# 9_3_2_detector_booster.net
KiCad netlist of a schematic drawn in EAGLE
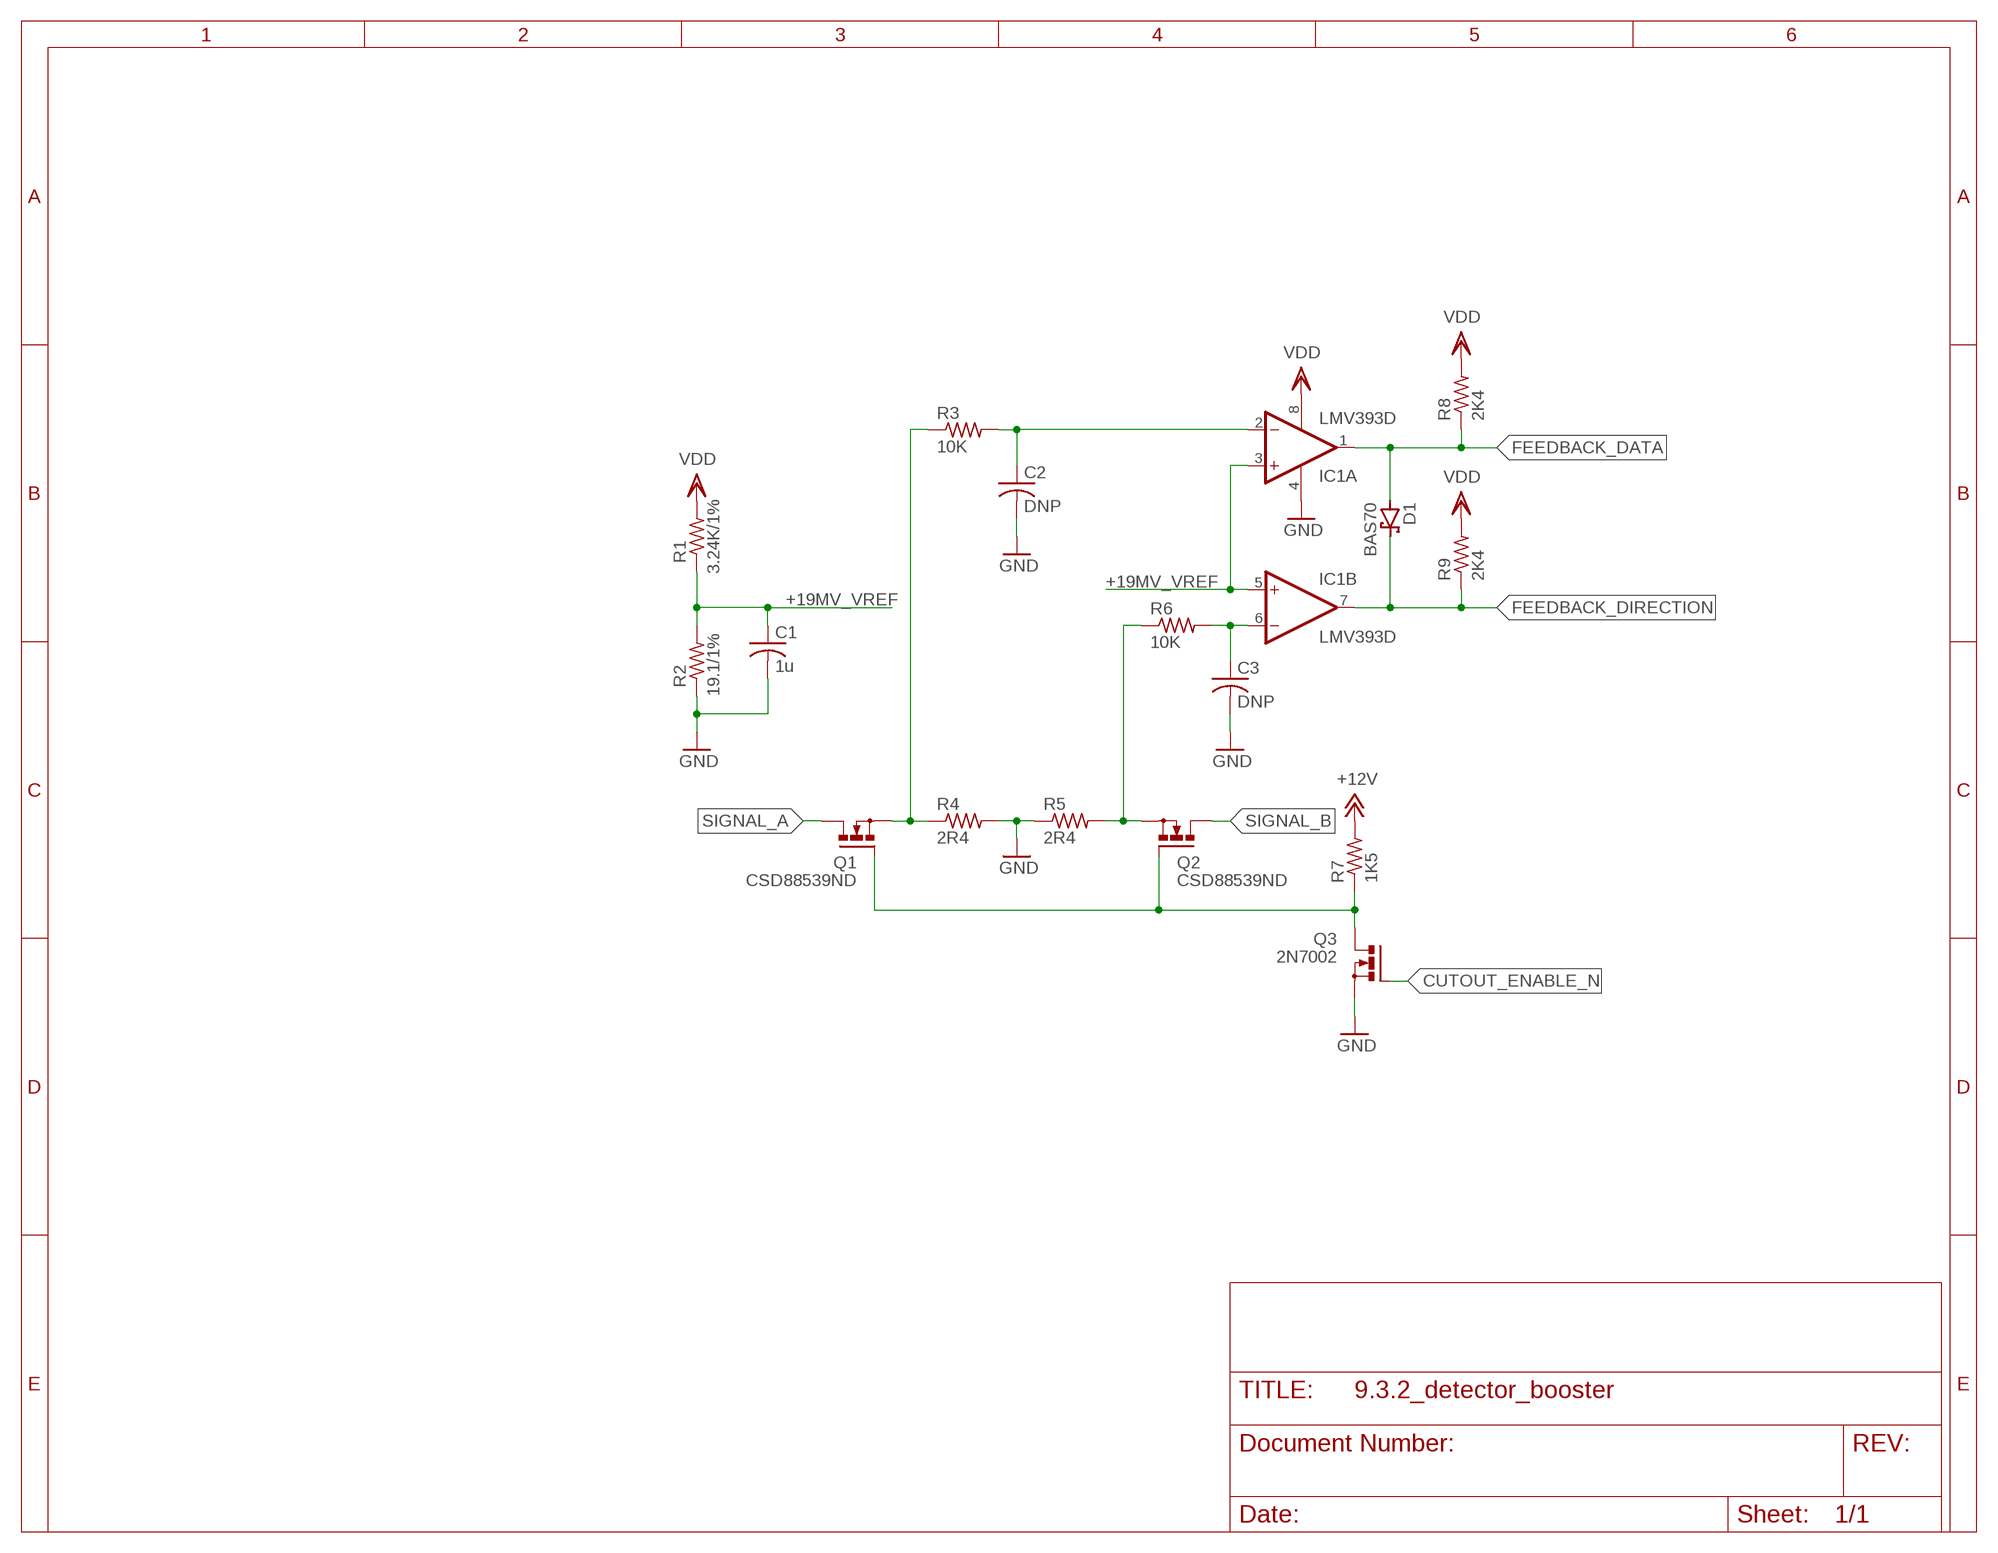
[diagram p0: schematic, sheet 1]

(export (version "E")
  (design (tool "Eeschema 10.0.6"))
  (components
    (comp (ref "C1")
      (value "1u")
      (footprint "eagle-import:C0402")
      (libsource (lib "eagle-import") (part "C-USC0402"))
    )
    (comp (ref "C2")
      (value "DNP")
      (footprint "eagle-import:C0402")
      (libsource (lib "eagle-import") (part "C-USC0402"))
    )
    (comp (ref "C3")
      (value "DNP")
      (footprint "eagle-import:C0402")
      (libsource (lib "eagle-import") (part "C-USC0402"))
    )
    (comp (ref "D1")
      (value "BAS70")
      (footprint "eagle-import:SOT23")
      (libsource (lib "eagle-import") (part "BAS70"))
    )
    (comp (ref "IC1")
      (value "LMV393D")
      (footprint "eagle-import:SO08")
      (libsource (lib "eagle-import") (part "LM393D"))
    )
    (comp (ref "Q1")
      (value "CSD88539ND")
      (footprint "eagle-import:TO220BV")
      (libsource (lib "eagle-import") (part "IRF512"))
    )
    (comp (ref "Q2")
      (value "CSD88539ND")
      (footprint "eagle-import:TO220BV")
      (libsource (lib "eagle-import") (part "IRF512"))
    )
    (comp (ref "Q3")
      (value "2N7002")
      (footprint "eagle-import:TO220BV")
      (libsource (lib "eagle-import") (part "IRF512"))
    )
    (comp (ref "R1")
      (value "3.24K/1%")
      (footprint "eagle-import:R0402")
      (libsource (lib "eagle-import") (part "R-US_R0402"))
    )
    (comp (ref "R2")
      (value "19.1/1%")
      (footprint "eagle-import:R0402")
      (libsource (lib "eagle-import") (part "R-US_R0402"))
    )
    (comp (ref "R3")
      (value "10K")
      (footprint "eagle-import:R0402")
      (libsource (lib "eagle-import") (part "R-US_R0402"))
    )
    (comp (ref "R4")
      (value "2R4")
      (footprint "eagle-import:R1206")
      (libsource (lib "eagle-import") (part "R-US_R1206"))
    )
    (comp (ref "R5")
      (value "2R4")
      (footprint "eagle-import:R1206")
      (libsource (lib "eagle-import") (part "R-US_R1206"))
    )
    (comp (ref "R6")
      (value "10K")
      (footprint "eagle-import:R0402")
      (libsource (lib "eagle-import") (part "R-US_R0402"))
    )
    (comp (ref "R7")
      (value "1K5")
      (footprint "eagle-import:R1206")
      (libsource (lib "eagle-import") (part "R-US_R1206"))
    )
    (comp (ref "R8")
      (value "2K4")
      (footprint "eagle-import:R0402")
      (libsource (lib "eagle-import") (part "R-US_R0402"))
    )
    (comp (ref "R9")
      (value "2K4")
      (footprint "eagle-import:R0402")
      (libsource (lib "eagle-import") (part "R-US_R0402"))
    )
  )
  (nets
    (net (code "1") (name "+12V") (class "Default")
      (node (ref "R7") (pin "2") (pinfunction "2_2") (pintype "passive"))
    )
    (net (code "2") (name "/+19MV_VREF") (class "Default")
      (node (ref "C1") (pin "1") (pinfunction "1_1") (pintype "passive"))
      (node (ref "IC1") (pin "3") (pinfunction "+IN_3") (pintype "input"))
      (node (ref "IC1") (pin "5") (pinfunction "+IN_5") (pintype "input"))
      (node (ref "R1") (pin "1") (pinfunction "1_1") (pintype "passive"))
      (node (ref "R2") (pin "2") (pinfunction "2_2") (pintype "passive"))
    )
    (net (code "3") (name "CUTOUT_ENABLE_N") (class "Default")
      (node (ref "Q3") (pin "G") (pinfunction "G_G") (pintype "passive"))
    )
    (net (code "4") (name "FEEDBACK_DATA") (class "Default")
      (node (ref "D1") (pin "1") (pinfunction "A_1") (pintype "passive"))
      (node (ref "IC1") (pin "1") (pinfunction "OUT_1") (pintype "output"))
      (node (ref "R8") (pin "1") (pinfunction "1_1") (pintype "passive"))
    )
    (net (code "5") (name "FEEDBACK_DIRECTION") (class "Default")
      (node (ref "D1") (pin "3") (pinfunction "C_3") (pintype "passive"))
      (node (ref "IC1") (pin "7") (pinfunction "OUT_7") (pintype "output"))
      (node (ref "R9") (pin "1") (pinfunction "1_1") (pintype "passive"))
    )
    (net (code "6") (name "GND") (class "Default")
      (node (ref "C1") (pin "2") (pinfunction "2_2") (pintype "passive"))
      (node (ref "C2") (pin "2") (pinfunction "2_2") (pintype "passive"))
      (node (ref "C3") (pin "2") (pinfunction "2_2") (pintype "passive"))
      (node (ref "IC1") (pin "4") (pinfunction "V-_4") (pintype "power_in"))
      (node (ref "Q3") (pin "S") (pinfunction "S_S") (pintype "passive"))
      (node (ref "R2") (pin "1") (pinfunction "1_1") (pintype "passive"))
      (node (ref "R4") (pin "2") (pinfunction "2_2") (pintype "passive"))
      (node (ref "R5") (pin "1") (pinfunction "1_1") (pintype "passive"))
    )
    (net (code "7") (name "Net-(IC1A--IN)") (class "Default")
      (node (ref "C2") (pin "1") (pinfunction "1_1") (pintype "passive"))
      (node (ref "IC1") (pin "2") (pinfunction "-IN_2") (pintype "input"))
      (node (ref "R3") (pin "2") (pinfunction "2_2") (pintype "passive"))
    )
    (net (code "8") (name "Net-(IC1B--IN)") (class "Default")
      (node (ref "C3") (pin "1") (pinfunction "1_1") (pintype "passive"))
      (node (ref "IC1") (pin "6") (pinfunction "-IN_6") (pintype "input"))
      (node (ref "R6") (pin "2") (pinfunction "2_2") (pintype "passive"))
    )
    (net (code "9") (name "Net-(Q1-PadG)") (class "Default")
      (node (ref "Q1") (pin "G") (pinfunction "G_G") (pintype "passive"))
      (node (ref "Q2") (pin "G") (pinfunction "G_G") (pintype "passive"))
      (node (ref "Q3") (pin "D") (pinfunction "D_D") (pintype "passive"))
      (node (ref "R7") (pin "1") (pinfunction "1_1") (pintype "passive"))
    )
    (net (code "10") (name "Net-(Q1-PadS)") (class "Default")
      (node (ref "Q1") (pin "S") (pinfunction "S_S") (pintype "passive"))
      (node (ref "R3") (pin "1") (pinfunction "1_1") (pintype "passive"))
      (node (ref "R4") (pin "1") (pinfunction "1_1") (pintype "passive"))
    )
    (net (code "11") (name "Net-(Q2-PadS)") (class "Default")
      (node (ref "Q2") (pin "S") (pinfunction "S_S") (pintype "passive"))
      (node (ref "R5") (pin "2") (pinfunction "2_2") (pintype "passive"))
      (node (ref "R6") (pin "1") (pinfunction "1_1") (pintype "passive"))
    )
    (net (code "12") (name "SIGNAL_A") (class "Default")
      (node (ref "Q1") (pin "D") (pinfunction "D_D") (pintype "passive"))
    )
    (net (code "13") (name "SIGNAL_B") (class "Default")
      (node (ref "Q2") (pin "D") (pinfunction "D_D") (pintype "passive"))
    )
    (net (code "14") (name "VDD") (class "Default")
      (node (ref "IC1") (pin "8") (pinfunction "V+_8") (pintype "power_in"))
      (node (ref "R1") (pin "2") (pinfunction "2_2") (pintype "passive"))
      (node (ref "R8") (pin "2") (pinfunction "2_2") (pintype "passive"))
      (node (ref "R9") (pin "2") (pinfunction "2_2") (pintype "passive"))
    )
  )
)
